# Port_Expander_Using_I2C.net
KiCad netlist of a schematic drawn in EAGLE
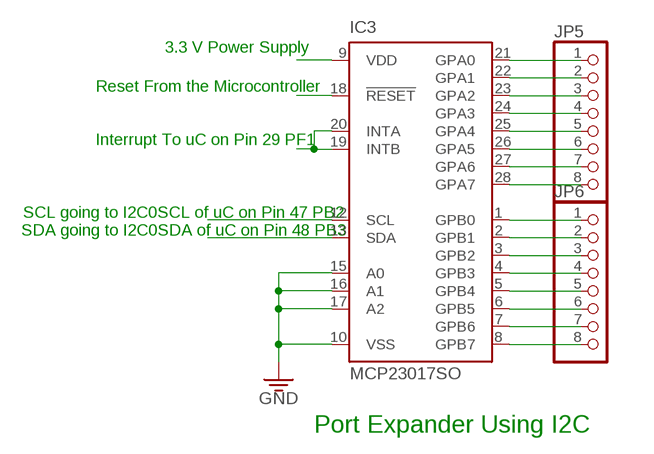
[diagram p0: schematic, sheet 1]

(export (version "E")
  (design (tool "Eeschema 10.0.6"))
  (components
    (comp (ref "IC3")
      (value "MCP23017SO")
      (footprint "eagle-import:SO28W")
      (libsource (lib "eagle-import") (part "MCP23017SO"))
    )
    (comp (ref "JP5")
      (value "PINHD-1X8BIG")
      (footprint "eagle-import:1X08-BIG")
      (libsource (lib "eagle-import") (part "PINHD-1X8BIG"))
    )
    (comp (ref "JP6")
      (value "PINHD-1X8BIG")
      (footprint "eagle-import:1X08-BIG")
      (libsource (lib "eagle-import") (part "PINHD-1X8BIG"))
    )
  )
  (nets
    (net (code "1") (name "GND") (class "Default")
      (node (ref "IC3") (pin "10") (pinfunction "VSS_10") (pintype "power_in"))
      (node (ref "IC3") (pin "15") (pinfunction "A0_15") (pintype "input"))
      (node (ref "IC3") (pin "16") (pinfunction "A1_16") (pintype "input"))
      (node (ref "IC3") (pin "17") (pinfunction "A2_17") (pintype "input"))
      (node (ref "IC3") (pin "9") (pinfunction "VDD_9") (pintype "power_in"))
    )
    (net (code "2") (name "Net-(IC3-GPA0)") (class "Default")
      (node (ref "IC3") (pin "21") (pinfunction "GPA0_21") (pintype "bidirectional"))
      (node (ref "JP5") (pin "1") (pinfunction "1_1") (pintype "passive"))
    )
    (net (code "3") (name "Net-(IC3-GPA1)") (class "Default")
      (node (ref "IC3") (pin "22") (pinfunction "GPA1_22") (pintype "bidirectional"))
      (node (ref "JP5") (pin "2") (pinfunction "2_2") (pintype "passive"))
    )
    (net (code "4") (name "Net-(IC3-GPA2)") (class "Default")
      (node (ref "IC3") (pin "23") (pinfunction "GPA2_23") (pintype "bidirectional"))
      (node (ref "JP5") (pin "3") (pinfunction "3_3") (pintype "passive"))
    )
    (net (code "5") (name "Net-(IC3-GPA3)") (class "Default")
      (node (ref "IC3") (pin "24") (pinfunction "GPA3_24") (pintype "bidirectional"))
      (node (ref "JP5") (pin "4") (pinfunction "4_4") (pintype "passive"))
    )
    (net (code "6") (name "Net-(IC3-GPA4)") (class "Default")
      (node (ref "IC3") (pin "25") (pinfunction "GPA4_25") (pintype "bidirectional"))
      (node (ref "JP5") (pin "5") (pinfunction "5_5") (pintype "passive"))
    )
    (net (code "7") (name "Net-(IC3-GPA5)") (class "Default")
      (node (ref "IC3") (pin "26") (pinfunction "GPA5_26") (pintype "bidirectional"))
      (node (ref "JP5") (pin "6") (pinfunction "6_6") (pintype "passive"))
    )
    (net (code "8") (name "Net-(IC3-GPA6)") (class "Default")
      (node (ref "IC3") (pin "27") (pinfunction "GPA6_27") (pintype "bidirectional"))
      (node (ref "JP5") (pin "7") (pinfunction "7_7") (pintype "passive"))
    )
    (net (code "9") (name "Net-(IC3-GPA7)") (class "Default")
      (node (ref "IC3") (pin "28") (pinfunction "GPA7_28") (pintype "bidirectional"))
      (node (ref "JP5") (pin "8") (pinfunction "8_8") (pintype "passive"))
    )
    (net (code "10") (name "Net-(IC3-GPB0)") (class "Default")
      (node (ref "IC3") (pin "1") (pinfunction "GPB0_1") (pintype "bidirectional"))
      (node (ref "JP6") (pin "1") (pinfunction "1_1") (pintype "passive"))
    )
    (net (code "11") (name "Net-(IC3-GPB1)") (class "Default")
      (node (ref "IC3") (pin "2") (pinfunction "GPB1_2") (pintype "bidirectional"))
      (node (ref "JP6") (pin "2") (pinfunction "2_2") (pintype "passive"))
    )
    (net (code "12") (name "Net-(IC3-GPB2)") (class "Default")
      (node (ref "IC3") (pin "3") (pinfunction "GPB2_3") (pintype "bidirectional"))
      (node (ref "JP6") (pin "3") (pinfunction "3_3") (pintype "passive"))
    )
    (net (code "13") (name "Net-(IC3-GPB3)") (class "Default")
      (node (ref "IC3") (pin "4") (pinfunction "GPB3_4") (pintype "bidirectional"))
      (node (ref "JP6") (pin "4") (pinfunction "4_4") (pintype "passive"))
    )
    (net (code "14") (name "Net-(IC3-GPB4)") (class "Default")
      (node (ref "IC3") (pin "5") (pinfunction "GPB4_5") (pintype "bidirectional"))
      (node (ref "JP6") (pin "5") (pinfunction "5_5") (pintype "passive"))
    )
    (net (code "15") (name "Net-(IC3-GPB5)") (class "Default")
      (node (ref "IC3") (pin "6") (pinfunction "GPB5_6") (pintype "bidirectional"))
      (node (ref "JP6") (pin "6") (pinfunction "6_6") (pintype "passive"))
    )
    (net (code "16") (name "Net-(IC3-GPB6)") (class "Default")
      (node (ref "IC3") (pin "7") (pinfunction "GPB6_7") (pintype "bidirectional"))
      (node (ref "JP6") (pin "7") (pinfunction "7_7") (pintype "passive"))
    )
    (net (code "17") (name "Net-(IC3-GPB7)") (class "Default")
      (node (ref "IC3") (pin "8") (pinfunction "GPB7_8") (pintype "bidirectional"))
      (node (ref "JP6") (pin "8") (pinfunction "8_8") (pintype "passive"))
    )
    (net (code "18") (name "Net-(IC3-INTA)") (class "Default")
      (node (ref "IC3") (pin "19") (pinfunction "INTB_19") (pintype "output"))
      (node (ref "IC3") (pin "20") (pinfunction "INTA_20") (pintype "output"))
    )
    (net (code "19") (name "unconnected-(IC3-SCL-Pad12)") (class "Default")
      (node (ref "IC3") (pin "12") (pinfunction "SCL_12") (pintype "input"))
    )
    (net (code "20") (name "unconnected-(IC3-SDA-Pad13)") (class "Default")
      (node (ref "IC3") (pin "13") (pinfunction "SDA_13") (pintype "bidirectional"))
    )
    (net (code "21") (name "unconnected-(IC3-~{RESET}-Pad18)") (class "Default")
      (node (ref "IC3") (pin "18") (pinfunction "~{RESET}_18") (pintype "input"))
    )
  )
)
